# 5_-CONNECTORS.net
KiCad netlist of a schematic drawn in Altium Designer
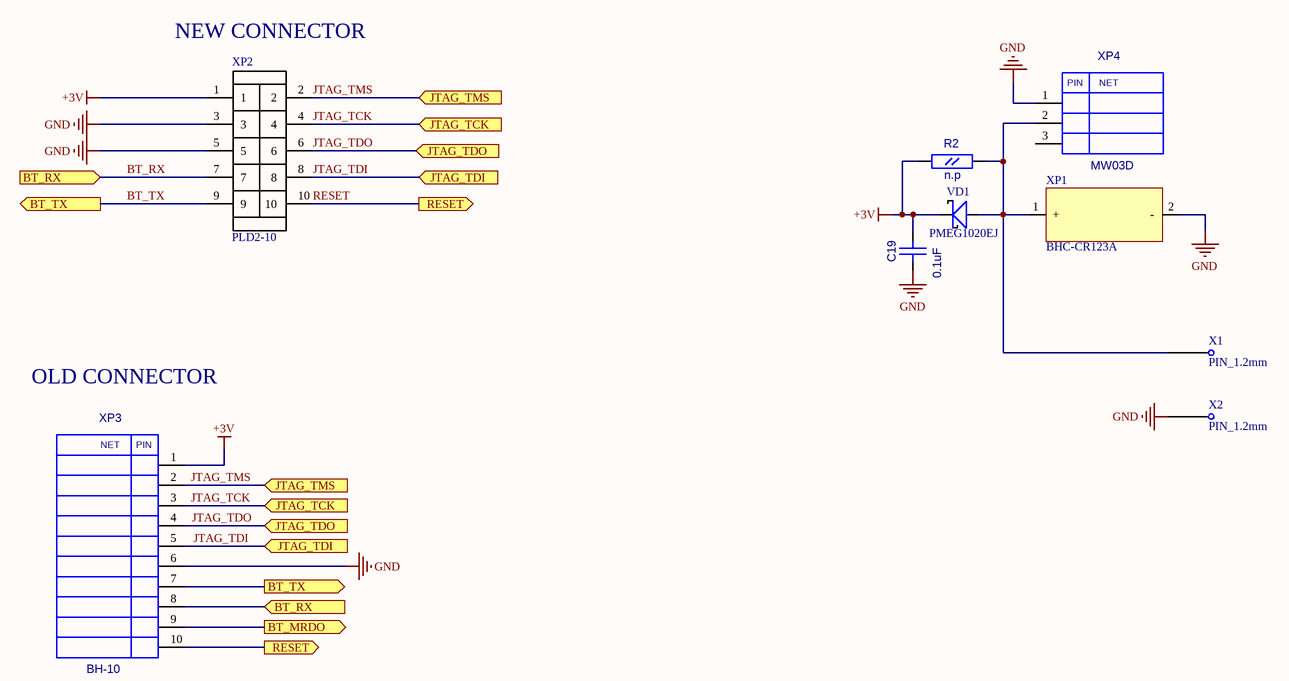
[diagram p0: [5]-CONNECTORS.SchDoc]

(export (version "E")
  (design (tool "Eeschema 10.0.6"))
  (components
    (comp (ref "C19")
      (value "0.1uF")
      (footprint "CC0603")
      (description "CC0603")
      (libsource (lib "fizik_lib") (part "CC0603"))
    )
    (comp (ref "R2")
      (value "n.p")
      (footprint "RC0603")
      (description "RC0603")
      (libsource (lib "fizik_lib") (part "RC0603"))
    )
    (comp (ref "VD1")
      (value "PMEG1020EJ")
      (footprint "SOD323")
      (libsource (lib "fizik_lib") (part "PMEG2010"))
    )
    (comp (ref "X1")
      (value "PIN_1.2mm")
      (footprint "PIN_1.2mm")
      (libsource (lib "fizik_lib") (part "PIN_1.2mm"))
    )
    (comp (ref "X2")
      (value "PIN_1.2mm")
      (footprint "PIN_1.2mm")
      (libsource (lib "fizik_lib") (part "PIN_1.2mm"))
    )
    (comp (ref "XP1")
      (value "BHC-CR123A")
      (footprint "CR123_HOLDER")
      (description "Holder for CR123 battery")
      (libsource (lib "fizik_lib") (part "BHC-CR123A"))
    )
    (comp (ref "XP2")
      (value "PLD2-10")
      (footprint "PLD2-10")
      (libsource (lib "gprs_modem_2") (part "PLD2-10"))
    )
    (comp (ref "XP3") (value "BH-10") (footprint "BH-10") (libsource (lib "gprs_modem_2") (part "BH-10")))
    (comp (ref "XP4") (value "MW03D") (footprint "MW03D") (libsource (lib "gprs_modem_2") (part "MW03D")))
  )
  (nets
    (net (code "1") (name "+3V") (class "Default")
      (node (ref "C19") (pin "2") (pinfunction "B_2") (pintype "passive"))
      (node (ref "R2") (pin "1") (pinfunction "A_1") (pintype "passive"))
      (node (ref "VD1") (pin "2") (pinfunction "K_2") (pintype "passive"))
      (node (ref "XP2") (pin "1") (pinfunction "1_1") (pintype "passive"))
      (node (ref "XP3") (pin "1") (pinfunction "1_1") (pintype "passive"))
    )
    (net (code "2") (name "/BT_MRDO") (class "Default")
      (node (ref "XP3") (pin "9") (pinfunction "9_9") (pintype "passive"))
    )
    (net (code "3") (name "/BT_RX") (class "Default")
      (node (ref "XP2") (pin "7") (pinfunction "7_7") (pintype "passive"))
      (node (ref "XP3") (pin "8") (pinfunction "8_8") (pintype "passive"))
    )
    (net (code "4") (name "/BT_TX") (class "Default")
      (node (ref "XP2") (pin "9") (pinfunction "9_9") (pintype "passive"))
      (node (ref "XP3") (pin "7") (pinfunction "7_7") (pintype "passive"))
    )
    (net (code "5") (name "/JTAG_TCK") (class "Default")
      (node (ref "XP2") (pin "4") (pinfunction "4_4") (pintype "passive"))
      (node (ref "XP3") (pin "3") (pinfunction "3_3") (pintype "passive"))
    )
    (net (code "6") (name "/JTAG_TDI") (class "Default")
      (node (ref "XP2") (pin "8") (pinfunction "8_8") (pintype "passive"))
      (node (ref "XP3") (pin "5") (pinfunction "5_5") (pintype "passive"))
    )
    (net (code "7") (name "/JTAG_TDO") (class "Default")
      (node (ref "XP2") (pin "6") (pinfunction "6_6") (pintype "passive"))
      (node (ref "XP3") (pin "4") (pinfunction "4_4") (pintype "passive"))
    )
    (net (code "8") (name "/JTAG_TMS") (class "Default")
      (node (ref "XP2") (pin "2") (pinfunction "2_2") (pintype "passive"))
      (node (ref "XP3") (pin "2") (pinfunction "2_2") (pintype "passive"))
    )
    (net (code "9") (name "/RESET") (class "Default")
      (node (ref "XP2") (pin "10") (pinfunction "10_10") (pintype "passive"))
      (node (ref "XP3") (pin "10") (pinfunction "10_10") (pintype "passive"))
    )
    (net (code "10") (name "GND") (class "Default")
      (node (ref "C19") (pin "1") (pinfunction "A_1") (pintype "passive"))
      (node (ref "X2") (pin "1") (pinfunction "1_1") (pintype "passive"))
      (node (ref "XP1") (pin "2") (pinfunction "-_2") (pintype "passive"))
      (node (ref "XP2") (pin "3") (pinfunction "3_3") (pintype "passive"))
      (node (ref "XP2") (pin "5") (pinfunction "5_5") (pintype "passive"))
      (node (ref "XP3") (pin "6") (pinfunction "6_6") (pintype "passive"))
      (node (ref "XP4") (pin "1") (pinfunction "1_1") (pintype "passive"))
    )
    (net (code "11") (name "Net-(R2-B)") (class "Default")
      (node (ref "R2") (pin "2") (pinfunction "B_2") (pintype "passive"))
      (node (ref "VD1") (pin "1") (pinfunction "A_1") (pintype "passive"))
      (node (ref "X1") (pin "1") (pinfunction "1_1") (pintype "passive"))
      (node (ref "XP1") (pin "1") (pinfunction "+_1") (pintype "passive"))
      (node (ref "XP4") (pin "2") (pinfunction "2_2") (pintype "passive"))
    )
    (net (code "12") (name "unconnected-(XP4-Pad3)") (class "Default")
      (node (ref "XP4") (pin "3") (pinfunction "3_3") (pintype "passive"))
    )
  )
)
